# M163X.net
KiCad netlist of a schematic drawn in EAGLE
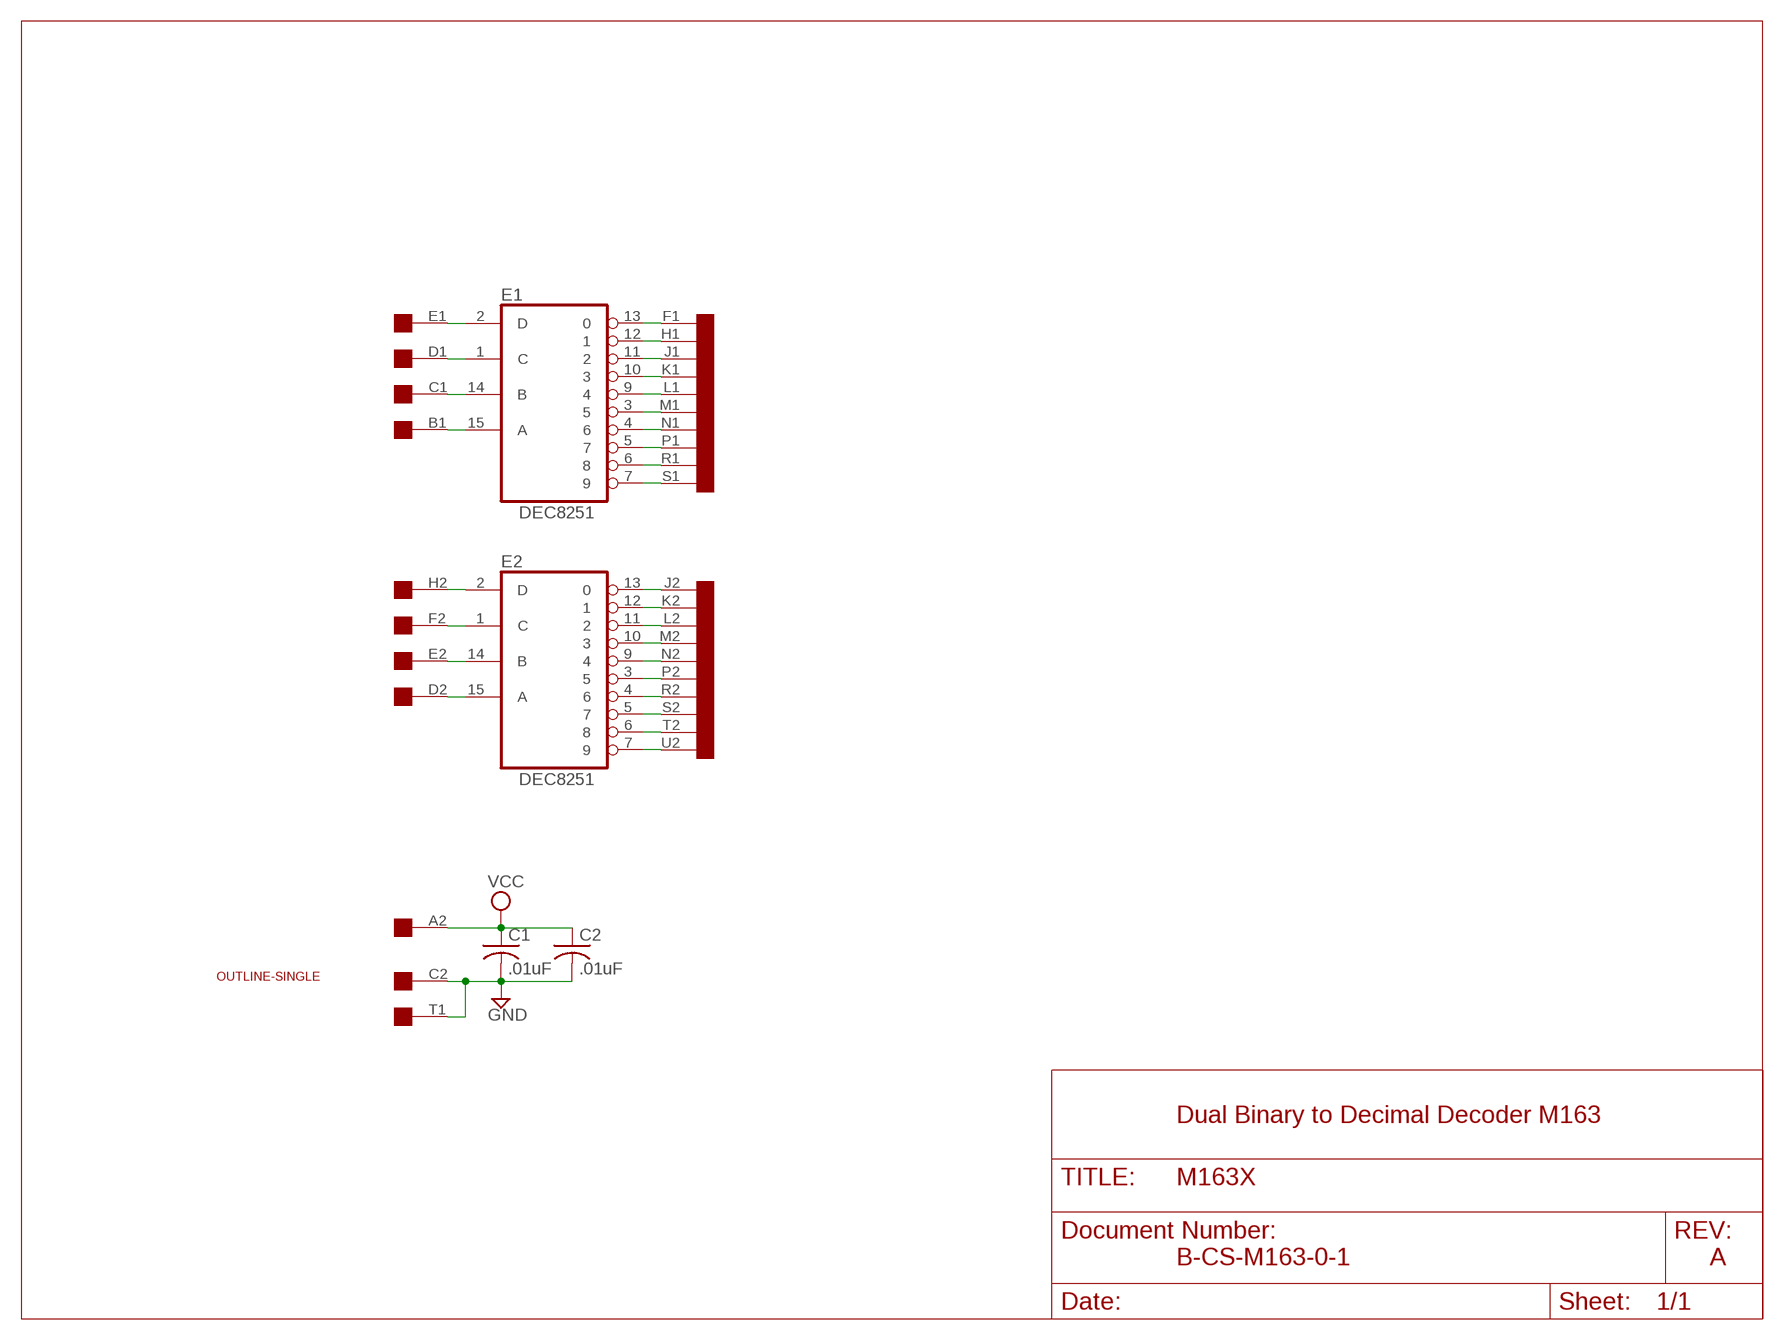
[diagram p0: schematic, sheet 1]

(export (version "E")
  (design (tool "Eeschema 10.0.6"))
  (components
    (comp (ref "C1")
      (value ".01uF")
      (footprint "eagle-import:C050-025X075")
      (libsource (lib "eagle-import") (part "C-US050-025X075"))
    )
    (comp (ref "C2")
      (value ".01uF")
      (footprint "eagle-import:C050-025X075")
      (libsource (lib "eagle-import") (part "C-US050-025X075"))
    )
    (comp (ref "E1")
      (value "DEC8251")
      (footprint "eagle-import:DIL16")
      (libsource (lib "eagle-import") (part "DEC8251"))
    )
    (comp (ref "E2")
      (value "DEC8251")
      (footprint "eagle-import:DIL16")
      (libsource (lib "eagle-import") (part "DEC8251"))
    )
    (comp (ref "U$1")
      (value "OUTLINE-SINGLE")
      (footprint "eagle-import:SINGLE")
      (libsource (lib "eagle-import") (part "OUTLINE-SINGLE"))
    )
    (comp (ref "U$2")
      (value "SINGLE")
      (footprint "eagle-import:EDGE-CON2")
      (libsource (lib "eagle-import") (part "SINGLE"))
    )
  )
  (nets
    (net (code "1") (name "GND") (class "Default")
      (node (ref "C1") (pin "2") (pinfunction "2_2") (pintype "passive"))
      (node (ref "C2") (pin "2") (pinfunction "2_2") (pintype "passive"))
      (node (ref "U$2") (pin "C2") (pinfunction "1_C2") (pintype "bidirectional"))
      (node (ref "U$2") (pin "T1") (pinfunction "1_T1") (pintype "bidirectional"))
    )
    (net (code "2") (name "Net-(E1A-0)") (class "Default")
      (node (ref "E1") (pin "13") (pinfunction "0_13") (pintype "output"))
      (node (ref "U$2") (pin "F1") (pinfunction "1_F1") (pintype "bidirectional"))
    )
    (net (code "3") (name "Net-(E1A-1)") (class "Default")
      (node (ref "E1") (pin "12") (pinfunction "1_12") (pintype "output"))
      (node (ref "U$2") (pin "H1") (pinfunction "1_H1") (pintype "bidirectional"))
    )
    (net (code "4") (name "Net-(E1A-2)") (class "Default")
      (node (ref "E1") (pin "11") (pinfunction "2_11") (pintype "output"))
      (node (ref "U$2") (pin "J1") (pinfunction "1_J1") (pintype "bidirectional"))
    )
    (net (code "5") (name "Net-(E1A-3)") (class "Default")
      (node (ref "E1") (pin "10") (pinfunction "3_10") (pintype "output"))
      (node (ref "U$2") (pin "K1") (pinfunction "1_K1") (pintype "bidirectional"))
    )
    (net (code "6") (name "Net-(E1A-4)") (class "Default")
      (node (ref "E1") (pin "9") (pinfunction "4_9") (pintype "output"))
      (node (ref "U$2") (pin "L1") (pinfunction "1_L1") (pintype "bidirectional"))
    )
    (net (code "7") (name "Net-(E1A-5)") (class "Default")
      (node (ref "E1") (pin "3") (pinfunction "5_3") (pintype "output"))
      (node (ref "U$2") (pin "M1") (pinfunction "1_M1") (pintype "bidirectional"))
    )
    (net (code "8") (name "Net-(E1A-6)") (class "Default")
      (node (ref "E1") (pin "4") (pinfunction "6_4") (pintype "output"))
      (node (ref "U$2") (pin "N1") (pinfunction "1_N1") (pintype "bidirectional"))
    )
    (net (code "9") (name "Net-(E1A-7)") (class "Default")
      (node (ref "E1") (pin "5") (pinfunction "7_5") (pintype "output"))
      (node (ref "U$2") (pin "P1") (pinfunction "1_P1") (pintype "bidirectional"))
    )
    (net (code "10") (name "Net-(E1A-8)") (class "Default")
      (node (ref "E1") (pin "6") (pinfunction "8_6") (pintype "output"))
      (node (ref "U$2") (pin "R1") (pinfunction "1_R1") (pintype "bidirectional"))
    )
    (net (code "11") (name "Net-(E1A-9)") (class "Default")
      (node (ref "E1") (pin "7") (pinfunction "9_7") (pintype "output"))
      (node (ref "U$2") (pin "S1") (pinfunction "1_S1") (pintype "bidirectional"))
    )
    (net (code "12") (name "Net-(E1A-A)") (class "Default")
      (node (ref "E1") (pin "15") (pinfunction "A_15") (pintype "input"))
      (node (ref "U$2") (pin "B1") (pinfunction "1_B1") (pintype "bidirectional"))
    )
    (net (code "13") (name "Net-(E1A-B)") (class "Default")
      (node (ref "E1") (pin "14") (pinfunction "B_14") (pintype "input"))
      (node (ref "U$2") (pin "C1") (pinfunction "1_C1") (pintype "bidirectional"))
    )
    (net (code "14") (name "Net-(E1A-C)") (class "Default")
      (node (ref "E1") (pin "1") (pinfunction "C_1") (pintype "input"))
      (node (ref "U$2") (pin "D1") (pinfunction "1_D1") (pintype "bidirectional"))
    )
    (net (code "15") (name "Net-(E1A-D)") (class "Default")
      (node (ref "E1") (pin "2") (pinfunction "D_2") (pintype "input"))
      (node (ref "U$2") (pin "E1") (pinfunction "1_E1") (pintype "bidirectional"))
    )
    (net (code "16") (name "Net-(E2A-0)") (class "Default")
      (node (ref "E2") (pin "13") (pinfunction "0_13") (pintype "output"))
      (node (ref "U$2") (pin "J2") (pinfunction "1_J2") (pintype "bidirectional"))
    )
    (net (code "17") (name "Net-(E2A-1)") (class "Default")
      (node (ref "E2") (pin "12") (pinfunction "1_12") (pintype "output"))
      (node (ref "U$2") (pin "K2") (pinfunction "1_K2") (pintype "bidirectional"))
    )
    (net (code "18") (name "Net-(E2A-2)") (class "Default")
      (node (ref "E2") (pin "11") (pinfunction "2_11") (pintype "output"))
      (node (ref "U$2") (pin "L2") (pinfunction "1_L2") (pintype "bidirectional"))
    )
    (net (code "19") (name "Net-(E2A-3)") (class "Default")
      (node (ref "E2") (pin "10") (pinfunction "3_10") (pintype "output"))
      (node (ref "U$2") (pin "M2") (pinfunction "1_M2") (pintype "bidirectional"))
    )
    (net (code "20") (name "Net-(E2A-4)") (class "Default")
      (node (ref "E2") (pin "9") (pinfunction "4_9") (pintype "output"))
      (node (ref "U$2") (pin "N2") (pinfunction "1_N2") (pintype "bidirectional"))
    )
    (net (code "21") (name "Net-(E2A-5)") (class "Default")
      (node (ref "E2") (pin "3") (pinfunction "5_3") (pintype "output"))
      (node (ref "U$2") (pin "P2") (pinfunction "1_P2") (pintype "bidirectional"))
    )
    (net (code "22") (name "Net-(E2A-6)") (class "Default")
      (node (ref "E2") (pin "4") (pinfunction "6_4") (pintype "output"))
      (node (ref "U$2") (pin "R2") (pinfunction "1_R2") (pintype "bidirectional"))
    )
    (net (code "23") (name "Net-(E2A-7)") (class "Default")
      (node (ref "E2") (pin "5") (pinfunction "7_5") (pintype "output"))
      (node (ref "U$2") (pin "S2") (pinfunction "1_S2") (pintype "bidirectional"))
    )
    (net (code "24") (name "Net-(E2A-8)") (class "Default")
      (node (ref "E2") (pin "6") (pinfunction "8_6") (pintype "output"))
      (node (ref "U$2") (pin "T2") (pinfunction "1_T2") (pintype "bidirectional"))
    )
    (net (code "25") (name "Net-(E2A-9)") (class "Default")
      (node (ref "E2") (pin "7") (pinfunction "9_7") (pintype "output"))
      (node (ref "U$2") (pin "U2") (pinfunction "1_U2") (pintype "bidirectional"))
    )
    (net (code "26") (name "Net-(E2A-A)") (class "Default")
      (node (ref "E2") (pin "15") (pinfunction "A_15") (pintype "input"))
      (node (ref "U$2") (pin "D2") (pinfunction "1_D2") (pintype "bidirectional"))
    )
    (net (code "27") (name "Net-(E2A-B)") (class "Default")
      (node (ref "E2") (pin "14") (pinfunction "B_14") (pintype "input"))
      (node (ref "U$2") (pin "E2") (pinfunction "1_E2") (pintype "bidirectional"))
    )
    (net (code "28") (name "Net-(E2A-C)") (class "Default")
      (node (ref "E2") (pin "1") (pinfunction "C_1") (pintype "input"))
      (node (ref "U$2") (pin "F2") (pinfunction "1_F2") (pintype "bidirectional"))
    )
    (net (code "29") (name "Net-(E2A-D)") (class "Default")
      (node (ref "E2") (pin "2") (pinfunction "D_2") (pintype "input"))
      (node (ref "U$2") (pin "H2") (pinfunction "1_H2") (pintype "bidirectional"))
    )
    (net (code "30") (name "VCC") (class "Default")
      (node (ref "C1") (pin "1") (pinfunction "1_1") (pintype "passive"))
      (node (ref "C2") (pin "1") (pinfunction "1_1") (pintype "passive"))
      (node (ref "U$2") (pin "A2") (pinfunction "1_A2") (pintype "bidirectional"))
    )
  )
)
